# SpringReverbRev2_combined.net
KiCad netlist of a schematic drawn in EAGLE
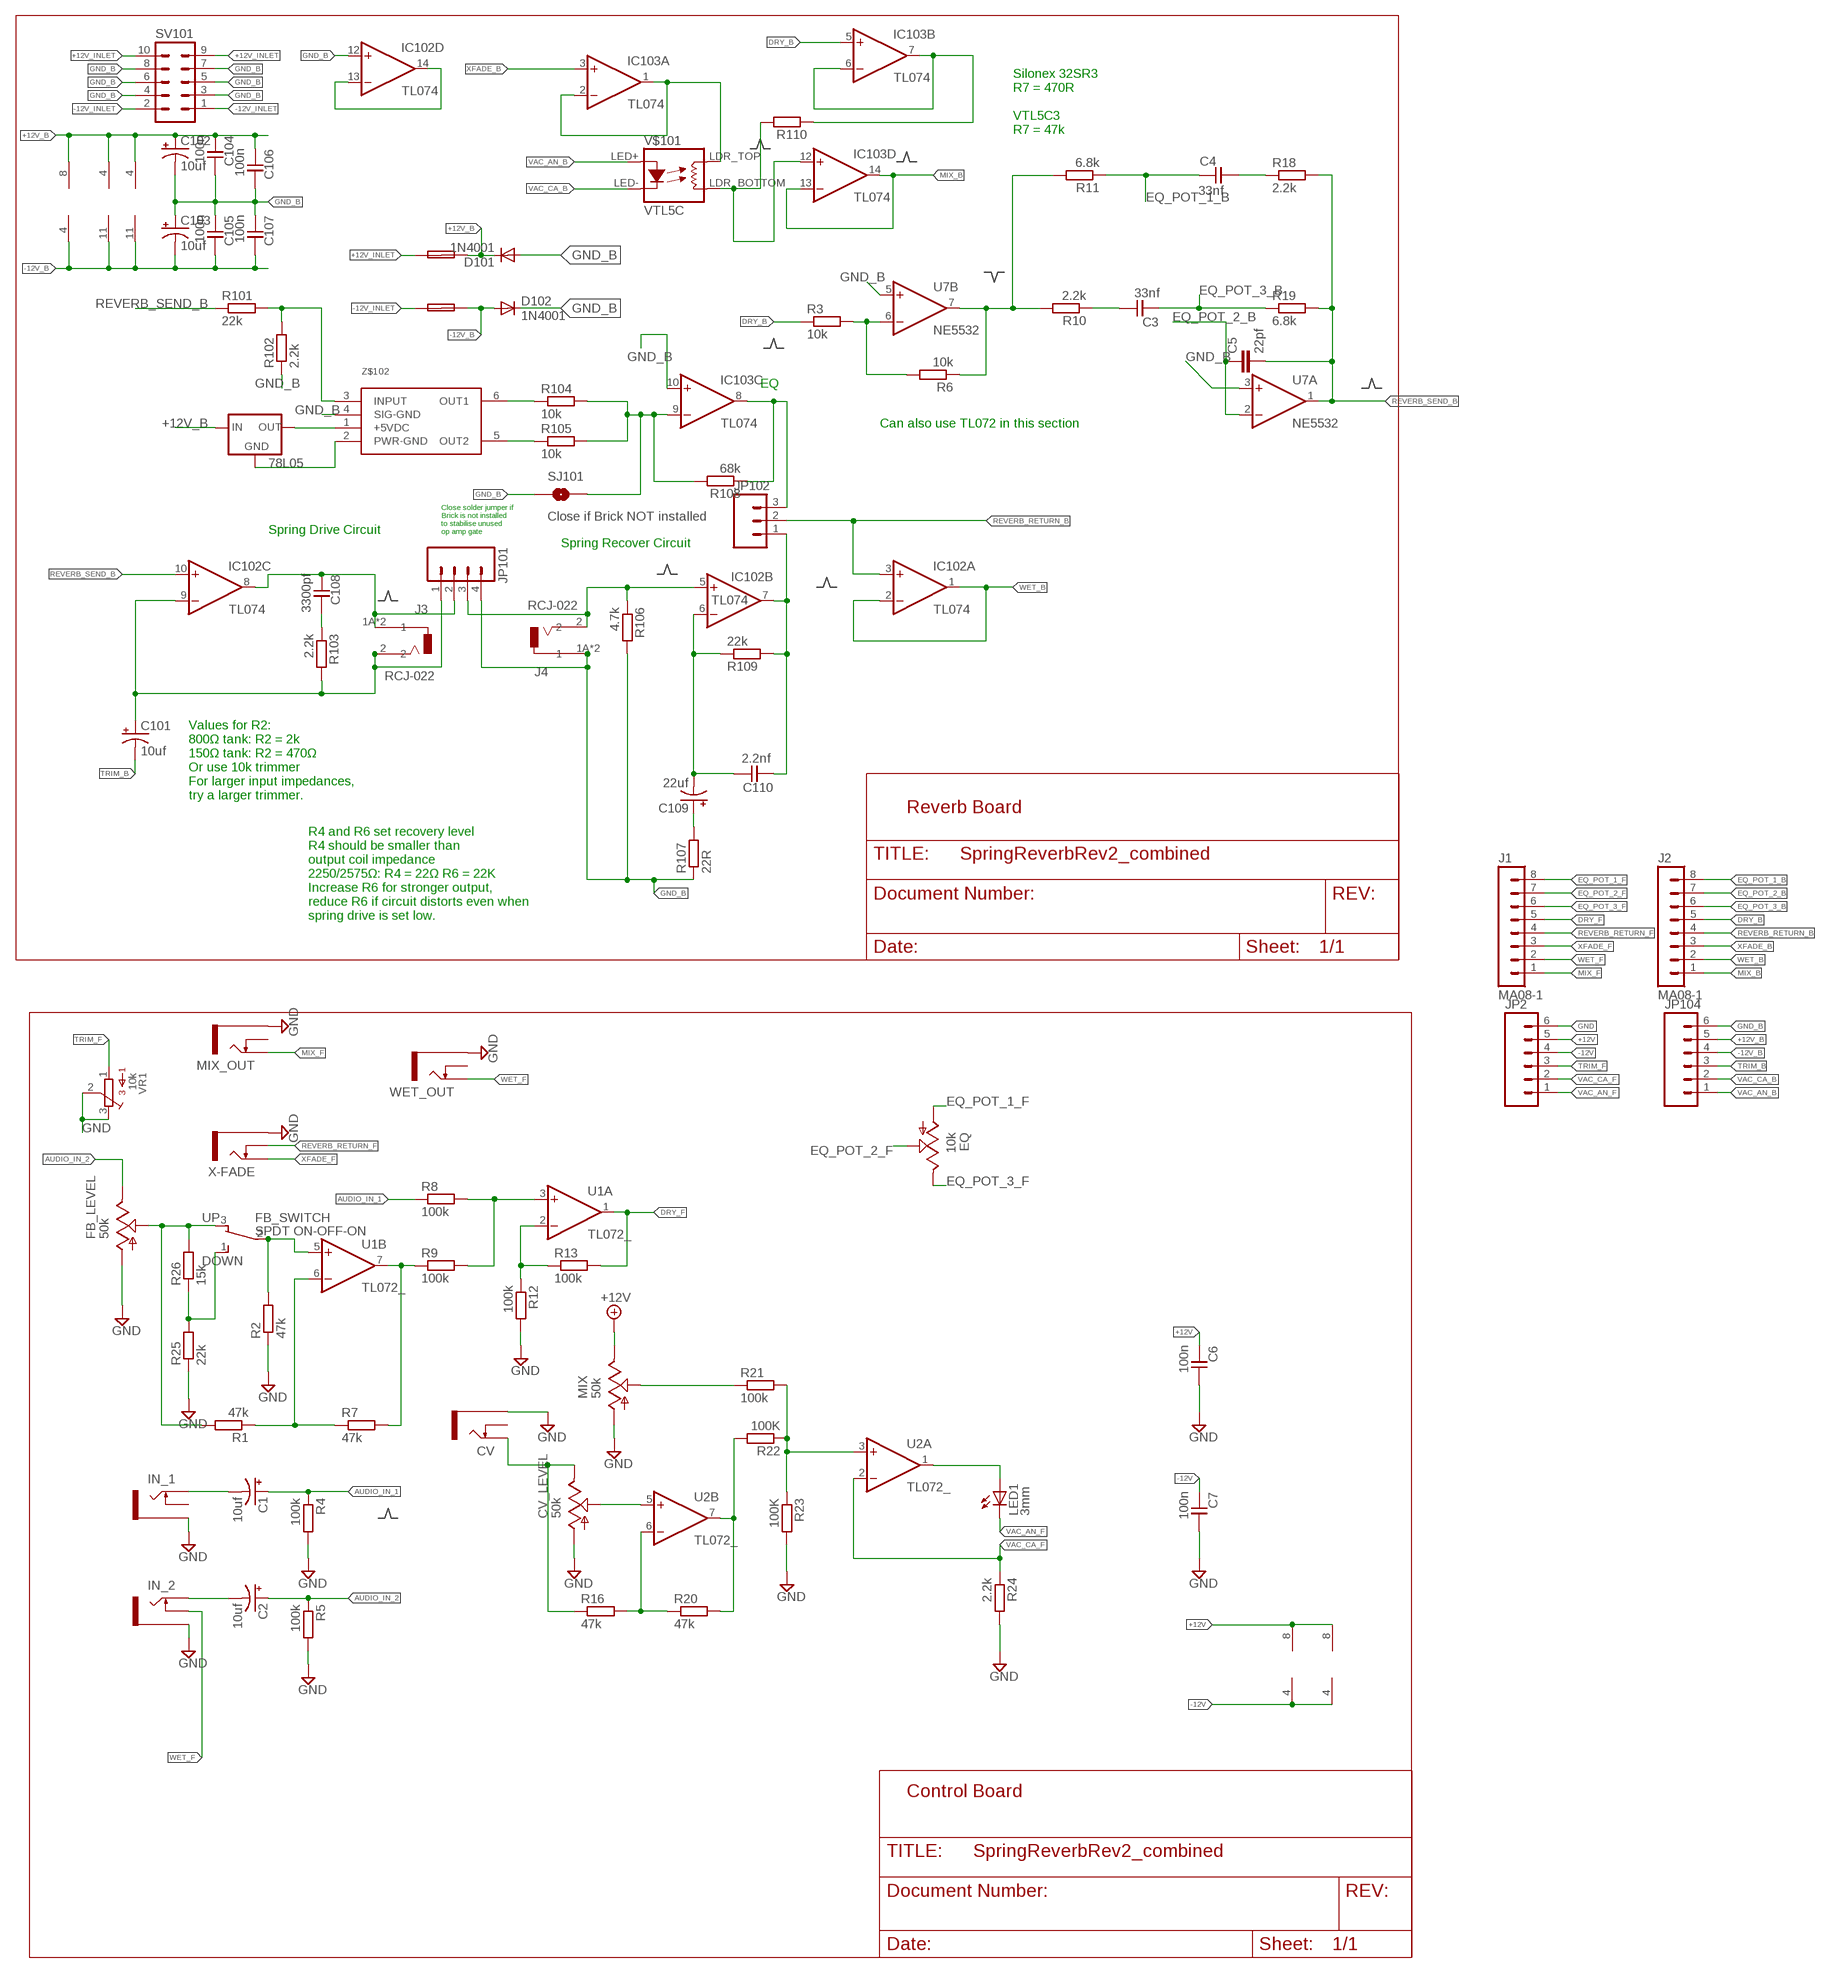
[diagram p0: schematic, sheet 1]

(export (version "E")
  (design (tool "Eeschema 10.0.6"))
  (components
    (comp (ref "78L05")
      (value "78LXX")
      (footprint "eagle-import:78LXX")
      (libsource (lib "eagle-import") (part "78LXX"))
    )
    (comp (ref "C1")
      (value "10uf")
      (footprint "eagle-import:050_020")
      (libsource (lib "eagle-import") (part "050"))
    )
    (comp (ref "C2")
      (value "10uf")
      (footprint "eagle-import:050_020")
      (libsource (lib "eagle-import") (part "050"))
    )
    (comp (ref "C3")
      (value "33nf")
      (footprint "eagle-import:C050-024X044")
      (libsource (lib "eagle-import") (part "C-EU050-024X044"))
    )
    (comp (ref "C4")
      (value "33nf")
      (footprint "eagle-import:C050-024X044")
      (libsource (lib "eagle-import") (part "C-EU050-024X044"))
    )
    (comp (ref "C5")
      (value "22pf")
      (footprint "eagle-import:050X030_025")
      (libsource (lib "eagle-import") (part "050X030_0251"))
    )
    (comp (ref "C6")
      (value "100n")
      (footprint "eagle-import:C050-024X044")
      (libsource (lib "eagle-import") (part "C-EU050-024X044"))
    )
    (comp (ref "C7")
      (value "100n")
      (footprint "eagle-import:C050-024X044")
      (libsource (lib "eagle-import") (part "C-EU050-024X044"))
    )
    (comp (ref "C101")
      (value "10uf")
      (footprint "eagle-import:CPOL-RADIAL-10UF-25V")
      (libsource (lib "eagle-import") (part "CAP_POLPTH2"))
    )
    (comp (ref "C102")
      (value "10uf")
      (footprint "eagle-import:CPOL-RADIAL-10UF-25V")
      (libsource (lib "eagle-import") (part "CAP_POLPTH2"))
    )
    (comp (ref "C103")
      (value "10uf")
      (footprint "eagle-import:CPOL-RADIAL-10UF-25V")
      (libsource (lib "eagle-import") (part "CAP_POLPTH2"))
    )
    (comp (ref "C104")
      (value "100n")
      (footprint "eagle-import:C050-024X044")
      (libsource (lib "eagle-import") (part "C-EU050-024X044"))
    )
    (comp (ref "C105")
      (value "100n")
      (footprint "eagle-import:C050-024X044")
      (libsource (lib "eagle-import") (part "C-EU050-024X044"))
    )
    (comp (ref "C106")
      (value "100n")
      (footprint "eagle-import:C050-024X044")
      (libsource (lib "eagle-import") (part "C-EU050-024X044"))
    )
    (comp (ref "C107")
      (value "100n")
      (footprint "eagle-import:C050-024X044")
      (libsource (lib "eagle-import") (part "C-EU050-024X044"))
    )
    (comp (ref "C108")
      (value "3300pf")
      (footprint "eagle-import:C050-024X044")
      (libsource (lib "eagle-import") (part "C-EU050-024X044"))
    )
    (comp (ref "C109")
      (value "22uf")
      (footprint "eagle-import:CPOL-RADIAL-10UF-25V")
      (libsource (lib "eagle-import") (part "CAP_POLPTH2"))
    )
    (comp (ref "C110")
      (value "2.2nf")
      (footprint "eagle-import:C050-024X044")
      (libsource (lib "eagle-import") (part "C-EU050-024X044"))
    )
    (comp (ref "CV")
      (value "THONKICONNNEW")
      (footprint "eagle-import:WQP-PJ301M-12_JACK")
      (libsource (lib "eagle-import") (part "THONKICONNNEW"))
    )
    (comp (ref "CV_LEVEL")
      (value "50k")
      (footprint "eagle-import:EVUF")
      (libsource (lib "eagle-import") (part "ALPHA-9MMAF2"))
    )
    (comp (ref "D101")
      (value "1N4001")
      (footprint "eagle-import:DO41-10")
      (libsource (lib "eagle-import") (part "1N4004"))
    )
    (comp (ref "D102")
      (value "1N4001")
      (footprint "eagle-import:DO41-10")
      (libsource (lib "eagle-import") (part "1N4004"))
    )
    (comp (ref "EQ")
      (value "10k")
      (footprint "eagle-import:EVUF")
      (libsource (lib "eagle-import") (part "ALPHA-9MMAF2"))
    )
    (comp (ref "F101")
      (value "FUSE")
      (footprint "eagle-import:C050H075X075")
      (libsource (lib "eagle-import") (part "PTC_FUSEPOLY_FUSE"))
    )
    (comp (ref "F102")
      (value "FUSE")
      (footprint "eagle-import:C050H075X075")
      (libsource (lib "eagle-import") (part "PTC_FUSEPOLY_FUSE"))
    )
    (comp (ref "FB_LEVEL")
      (value "50k")
      (footprint "eagle-import:EVUF")
      (libsource (lib "eagle-import") (part "ALPHA-9MMAF2"))
    )
    (comp (ref "FB_SWITCH")
      (value "SPDT ON-OFF-ON")
      (footprint "eagle-import:SPDT-VERTICAL-TOP-SUBMINI-MULTICOMP")
      (libsource (lib "eagle-import") (part "SPDT-VERTICAL-UPTOP-SUBMINI"))
    )
    (comp (ref "IC102")
      (value "TL074")
      (footprint "eagle-import:DIL14")
      (libsource (lib "eagle-import") (part "TL074P"))
    )
    (comp (ref "IC103")
      (value "TL074")
      (footprint "eagle-import:DIL14")
      (libsource (lib "eagle-import") (part "TL074P"))
    )
    (comp (ref "IN_1")
      (value "THONKICONNNEW")
      (footprint "eagle-import:WQP-PJ301M-12_JACK")
      (libsource (lib "eagle-import") (part "THONKICONNNEW"))
    )
    (comp (ref "IN_2")
      (value "THONKICONNNEW")
      (footprint "eagle-import:WQP-PJ301M-12_JACK")
      (libsource (lib "eagle-import") (part "THONKICONNNEW"))
    )
    (comp (ref "J1")
      (value "MA08-1")
      (footprint "eagle-import:MA08-1")
      (libsource (lib "eagle-import") (part "MA08-1"))
    )
    (comp (ref "J2")
      (value "MA08-1")
      (footprint "eagle-import:MA08-1")
      (libsource (lib "eagle-import") (part "MA08-1"))
    )
    (comp (ref "J3")
      (value "RCJ-022")
      (footprint "eagle-import:CUI_RCJ-022")
      (fields (field (name "MANUFACTURER") "CUI Inc"))
      (libsource (lib "eagle-import") (part "RCJ-022"))
    )
    (comp (ref "J4")
      (value "RCJ-022")
      (footprint "eagle-import:CUI_RCJ-022")
      (fields (field (name "MANUFACTURER") "CUI Inc"))
      (libsource (lib "eagle-import") (part "RCJ-022"))
    )
    (comp (ref "JP2")
      (value "M06SIP")
      (footprint "eagle-import:1X06")
      (libsource (lib "eagle-import") (part "M06SIP"))
    )
    (comp (ref "JP101")
      (value "M04POLAR")
      (footprint "eagle-import:MOLEX-1X4")
      (libsource (lib "eagle-import") (part "M04POLAR"))
    )
    (comp (ref "JP102")
      (value "M03LOCK_NO_SILK")
      (footprint "eagle-import:1X03_LOCK_NO_SILK")
      (libsource (lib "eagle-import") (part "M03LOCK_NO_SILK"))
    )
    (comp (ref "JP104")
      (value "M06SIP")
      (footprint "eagle-import:1X06")
      (libsource (lib "eagle-import") (part "M06SIP"))
    )
    (comp (ref "LED1")
      (value "3mm")
      (footprint "eagle-import:LED3MM")
      (libsource (lib "eagle-import") (part "LED3MM"))
    )
    (comp (ref "MIX")
      (value "50k")
      (footprint "eagle-import:EVUF")
      (libsource (lib "eagle-import") (part "ALPHA-9MMAF2"))
    )
    (comp (ref "MIX_OUT")
      (value "THONKICONNNEW")
      (footprint "eagle-import:WQP-PJ301M-12_JACK")
      (libsource (lib "eagle-import") (part "THONKICONNNEW"))
    )
    (comp (ref "R1")
      (value "47k")
      (footprint "eagle-import:7MM_RESISTOR")
      (libsource (lib "eagle-import") (part "RESISTOR7MM"))
    )
    (comp (ref "R2")
      (value "47k")
      (footprint "eagle-import:7MM_RESISTOR")
      (libsource (lib "eagle-import") (part "RESISTOR7MM"))
    )
    (comp (ref "R3")
      (value "10k")
      (footprint "eagle-import:7MM_RESISTOR")
      (libsource (lib "eagle-import") (part "RESISTOR7MM"))
    )
    (comp (ref "R4")
      (value "100k")
      (footprint "eagle-import:7MM_RESISTOR")
      (libsource (lib "eagle-import") (part "RESISTOR7MM"))
    )
    (comp (ref "R5")
      (value "100k")
      (footprint "eagle-import:7MM_RESISTOR")
      (libsource (lib "eagle-import") (part "RESISTOR7MM"))
    )
    (comp (ref "R6")
      (value "10k")
      (footprint "eagle-import:7MM_RESISTOR")
      (libsource (lib "eagle-import") (part "RESISTOR7MM"))
    )
    (comp (ref "R7")
      (value "47k")
      (footprint "eagle-import:7MM_RESISTOR")
      (libsource (lib "eagle-import") (part "RESISTOR7MM"))
    )
    (comp (ref "R8")
      (value "100k")
      (footprint "eagle-import:7MM_RESISTOR")
      (libsource (lib "eagle-import") (part "RESISTOR7MM"))
    )
    (comp (ref "R9")
      (value "100k")
      (footprint "eagle-import:7MM_RESISTOR")
      (libsource (lib "eagle-import") (part "RESISTOR7MM"))
    )
    (comp (ref "R10")
      (value "2.2k")
      (footprint "eagle-import:7MM_RESISTOR")
      (libsource (lib "eagle-import") (part "RESISTOR7MM"))
    )
    (comp (ref "R11")
      (value "6.8k")
      (footprint "eagle-import:7MM_RESISTOR")
      (libsource (lib "eagle-import") (part "RESISTOR7MM"))
    )
    (comp (ref "R12")
      (value "100k")
      (footprint "eagle-import:7MM_RESISTOR")
      (libsource (lib "eagle-import") (part "RESISTOR7MM"))
    )
    (comp (ref "R13")
      (value "100k")
      (footprint "eagle-import:7MM_RESISTOR")
      (libsource (lib "eagle-import") (part "RESISTOR7MM"))
    )
    (comp (ref "R16")
      (value "47k")
      (footprint "eagle-import:7MM_RESISTOR")
      (libsource (lib "eagle-import") (part "RESISTOR7MM"))
    )
    (comp (ref "R18")
      (value "2.2k")
      (footprint "eagle-import:7MM_RESISTOR")
      (libsource (lib "eagle-import") (part "RESISTOR7MM"))
    )
    (comp (ref "R19")
      (value "6.8k")
      (footprint "eagle-import:7MM_RESISTOR")
      (libsource (lib "eagle-import") (part "RESISTOR7MM"))
    )
    (comp (ref "R20")
      (value "47k")
      (footprint "eagle-import:7MM_RESISTOR")
      (libsource (lib "eagle-import") (part "RESISTOR7MM"))
    )
    (comp (ref "R21")
      (value "100k")
      (footprint "eagle-import:7MM_RESISTOR")
      (libsource (lib "eagle-import") (part "RESISTOR7MM"))
    )
    (comp (ref "R22")
      (value "100K")
      (footprint "eagle-import:7MM_RESISTOR")
      (libsource (lib "eagle-import") (part "RESISTOR7MM"))
    )
    (comp (ref "R23")
      (value "100K")
      (footprint "eagle-import:7MM_RESISTOR")
      (libsource (lib "eagle-import") (part "RESISTOR7MM"))
    )
    (comp (ref "R24")
      (value "2.2k")
      (footprint "eagle-import:7MM_RESISTOR")
      (libsource (lib "eagle-import") (part "RESISTOR7MM"))
    )
    (comp (ref "R25")
      (value "22k")
      (footprint "eagle-import:7MM_RESISTOR")
      (libsource (lib "eagle-import") (part "RESISTOR7MM"))
    )
    (comp (ref "R26")
      (value "15k")
      (footprint "eagle-import:7MM_RESISTOR")
      (libsource (lib "eagle-import") (part "RESISTOR7MM"))
    )
    (comp (ref "R101")
      (value "22k")
      (footprint "eagle-import:7MM_RESISTOR")
      (libsource (lib "eagle-import") (part "RESISTOR7MM"))
    )
    (comp (ref "R102")
      (value "2.2k")
      (footprint "eagle-import:7MM_RESISTOR")
      (libsource (lib "eagle-import") (part "RESISTOR7MM"))
    )
    (comp (ref "R103")
      (value "2.2k")
      (footprint "eagle-import:7MM_RESISTOR")
      (libsource (lib "eagle-import") (part "RESISTOR7MM"))
    )
    (comp (ref "R104")
      (value "10k")
      (footprint "eagle-import:7MM_RESISTOR")
      (libsource (lib "eagle-import") (part "RESISTOR7MM"))
    )
    (comp (ref "R105")
      (value "10k")
      (footprint "eagle-import:7MM_RESISTOR")
      (libsource (lib "eagle-import") (part "RESISTOR7MM"))
    )
    (comp (ref "R106")
      (value "4.7k")
      (footprint "eagle-import:7MM_RESISTOR")
      (libsource (lib "eagle-import") (part "RESISTOR7MM"))
    )
    (comp (ref "R107")
      (value "22R")
      (footprint "eagle-import:7MM_RESISTOR")
      (libsource (lib "eagle-import") (part "RESISTOR7MM"))
    )
    (comp (ref "R108")
      (value "68k")
      (footprint "eagle-import:7MM_RESISTOR")
      (libsource (lib "eagle-import") (part "RESISTOR7MM"))
    )
    (comp (ref "R109")
      (value "22k")
      (footprint "eagle-import:7MM_RESISTOR")
      (libsource (lib "eagle-import") (part "RESISTOR7MM"))
    )
    (comp (ref "R110")
      (value "RESISTOR7MM")
      (footprint "eagle-import:7MM_RESISTOR")
      (libsource (lib "eagle-import") (part "RESISTOR7MM"))
    )
    (comp (ref "SJ101")
      (value "Close if Brick NOT installed")
      (footprint "eagle-import:SJ_2S-NOTRACE")
      (libsource (lib "eagle-import") (part "SOLDERJUMPERNC2"))
    )
    (comp (ref "SV101")
      (value "10_PIN_HEADER")
      (footprint "eagle-import:MA05-2")
      (libsource (lib "eagle-import") (part "10_PIN_HEADER"))
    )
    (comp (ref "U1")
      (value "TL072_")
      (footprint "eagle-import:DIL08")
      (libsource (lib "eagle-import") (part "TL072_"))
    )
    (comp (ref "U2")
      (value "TL072_")
      (footprint "eagle-import:DIL08")
      (libsource (lib "eagle-import") (part "TL072_"))
    )
    (comp (ref "U7")
      (value "NE5532")
      (footprint "eagle-import:DIL08")
      (libsource (lib "eagle-import") (part "TL072_"))
    )
    (comp (ref "V$101")
      (value "VTL5C")
      (footprint "eagle-import:VACTROL_COMPACT")
      (libsource (lib "eagle-import") (part "VACTROL_COMPACT"))
    )
    (comp (ref "VR1")
      (value "10k")
      (footprint "eagle-import:BOURNS_3362P_TRIMMER")
      (libsource (lib "eagle-import") (part "BOURNS_3362P_TRIMMERP"))
    )
    (comp (ref "WET_OUT")
      (value "THONKICONNNEW")
      (footprint "eagle-import:WQP-PJ301M-12_JACK")
      (libsource (lib "eagle-import") (part "THONKICONNNEW"))
    )
    (comp (ref "X-FADE")
      (value "THONKICONNNEW")
      (footprint "eagle-import:WQP-PJ301M-12_JACK")
      (libsource (lib "eagle-import") (part "THONKICONNNEW"))
    )
    (comp (ref "Z$102")
      (value "BTDR-2H")
      (footprint "eagle-import:BTDR-2H")
      (libsource (lib "eagle-import") (part "BTDR-2H"))
    )
  )
  (nets
    (net (code "1") (name "+12V") (class "Default")
      (node (ref "C6") (pin "2") (pinfunction "2_2") (pintype "passive"))
      (node (ref "JP2") (pin "5") (pinfunction "5_5") (pintype "passive"))
      (node (ref "MIX") (pin "3") (pinfunction "E_3") (pintype "passive"))
      (node (ref "U1") (pin "8") (pinfunction "V+_8") (pintype "power_in"))
      (node (ref "U2") (pin "8") (pinfunction "V+_8") (pintype "power_in"))
    )
    (net (code "2") (name "+12V_B") (class "Default")
      (node (ref "78L05") (pin "IN") (pinfunction "IN_IN") (pintype "input"))
      (node (ref "C102") (pin "1") (pinfunction "+_1") (pintype "passive"))
      (node (ref "C104") (pin "2") (pinfunction "2_2") (pintype "passive"))
      (node (ref "C106") (pin "2") (pinfunction "2_2") (pintype "passive"))
      (node (ref "D101") (pin "C") (pinfunction "C_C") (pintype "passive"))
      (node (ref "F101") (pin "1") (pinfunction "P$1_1") (pintype "bidirectional"))
      (node (ref "IC102") (pin "4") (pinfunction "V+_4") (pintype "power_in"))
      (node (ref "IC103") (pin "4") (pinfunction "V+_4") (pintype "power_in"))
      (node (ref "JP104") (pin "5") (pinfunction "5_5") (pintype "passive"))
      (node (ref "U7") (pin "8") (pinfunction "V+_8") (pintype "power_in"))
    )
    (net (code "3") (name "+12V_INLET") (class "Default")
      (node (ref "F101") (pin "2") (pinfunction "P$2_2") (pintype "bidirectional"))
      (node (ref "SV101") (pin "10") (pinfunction "10_10") (pintype "passive"))
      (node (ref "SV101") (pin "9") (pinfunction "9_9") (pintype "passive"))
    )
    (net (code "4") (name "-12V") (class "Default")
      (node (ref "C7") (pin "2") (pinfunction "2_2") (pintype "passive"))
      (node (ref "JP2") (pin "4") (pinfunction "4_4") (pintype "passive"))
      (node (ref "U1") (pin "4") (pinfunction "V-_4") (pintype "power_in"))
      (node (ref "U2") (pin "4") (pinfunction "V-_4") (pintype "power_in"))
    )
    (net (code "5") (name "-12V_B") (class "Default")
      (node (ref "C103") (pin "2") (pinfunction "-_2") (pintype "passive"))
      (node (ref "C105") (pin "1") (pinfunction "1_1") (pintype "passive"))
      (node (ref "C107") (pin "1") (pinfunction "1_1") (pintype "passive"))
      (node (ref "D102") (pin "A") (pinfunction "A_A") (pintype "passive"))
      (node (ref "F102") (pin "1") (pinfunction "P$1_1") (pintype "bidirectional"))
      (node (ref "IC102") (pin "11") (pinfunction "V-_11") (pintype "power_in"))
      (node (ref "IC103") (pin "11") (pinfunction "V-_11") (pintype "power_in"))
      (node (ref "JP104") (pin "4") (pinfunction "4_4") (pintype "passive"))
      (node (ref "U7") (pin "4") (pinfunction "V-_4") (pintype "power_in"))
    )
    (net (code "6") (name "-12V_INLET") (class "Default")
      (node (ref "F102") (pin "2") (pinfunction "P$2_2") (pintype "bidirectional"))
      (node (ref "SV101") (pin "1") (pinfunction "1_1") (pintype "passive"))
      (node (ref "SV101") (pin "2") (pinfunction "2_2") (pintype "passive"))
    )
    (net (code "7") (name "AUDIO_IN_1") (class "Default")
      (node (ref "C1") (pin "+") (pinfunction "+_+") (pintype "passive"))
      (node (ref "R4") (pin "1") (pinfunction "1_1") (pintype "passive"))
      (node (ref "R8") (pin "1") (pinfunction "1_1") (pintype "passive"))
    )
    (net (code "8") (name "AUDIO_IN_2") (class "Default")
      (node (ref "C2") (pin "+") (pinfunction "+_+") (pintype "passive"))
      (node (ref "FB_LEVEL") (pin "3") (pinfunction "E_3") (pintype "passive"))
      (node (ref "R5") (pin "1") (pinfunction "1_1") (pintype "passive"))
    )
    (net (code "9") (name "DRY_B") (class "Default")
      (node (ref "IC103") (pin "5") (pinfunction "+IN_5") (pintype "input"))
      (node (ref "J2") (pin "5") (pinfunction "5_5") (pintype "passive"))
      (node (ref "R3") (pin "1") (pinfunction "1_1") (pintype "passive"))
    )
    (net (code "10") (name "DRY_F") (class "Default")
      (node (ref "J1") (pin "5") (pinfunction "5_5") (pintype "passive"))
      (node (ref "R13") (pin "2") (pinfunction "2_2") (pintype "passive"))
      (node (ref "U1") (pin "1") (pinfunction "OUT_1") (pintype "output"))
    )
    (net (code "11") (name "EQ_POT_1_B") (class "Default")
      (node (ref "C4") (pin "2") (pinfunction "2_2") (pintype "passive"))
      (node (ref "J2") (pin "8") (pinfunction "8_8") (pintype "passive"))
      (node (ref "R11") (pin "1") (pinfunction "1_1") (pintype "passive"))
    )
    (net (code "12") (name "EQ_POT_1_F") (class "Default")
      (node (ref "EQ") (pin "1") (pinfunction "A_1") (pintype "passive"))
      (node (ref "J1") (pin "8") (pinfunction "8_8") (pintype "passive"))
    )
    (net (code "13") (name "EQ_POT_2_B") (class "Default")
      (node (ref "C5") (pin "1") (pinfunction "1_1") (pintype "passive"))
      (node (ref "J2") (pin "7") (pinfunction "7_7") (pintype "passive"))
      (node (ref "U7") (pin "2") (pinfunction "-IN_2") (pintype "input"))
    )
    (net (code "14") (name "EQ_POT_2_F") (class "Default")
      (node (ref "EQ") (pin "2") (pinfunction "S_2") (pintype "passive"))
      (node (ref "J1") (pin "7") (pinfunction "7_7") (pintype "passive"))
    )
    (net (code "15") (name "EQ_POT_3_B") (class "Default")
      (node (ref "C3") (pin "2") (pinfunction "2_2") (pintype "passive"))
      (node (ref "J2") (pin "6") (pinfunction "6_6") (pintype "passive"))
      (node (ref "R19") (pin "1") (pinfunction "1_1") (pintype "passive"))
    )
    (net (code "16") (name "EQ_POT_3_F") (class "Default")
      (node (ref "EQ") (pin "3") (pinfunction "E_3") (pintype "passive"))
      (node (ref "J1") (pin "6") (pinfunction "6_6") (pintype "passive"))
    )
    (net (code "17") (name "GND") (class "Default")
      (node (ref "C6") (pin "1") (pinfunction "1_1") (pintype "passive"))
      (node (ref "C7") (pin "1") (pinfunction "1_1") (pintype "passive"))
      (node (ref "CV") (pin "P$3_SLEEVE") (pinfunction "SLEEVE_P$3_SLEEVE") (pintype "passive"))
      (node (ref "CV_LEVEL") (pin "1") (pinfunction "A_1") (pintype "passive"))
      (node (ref "FB_LEVEL") (pin "1") (pinfunction "A_1") (pintype "passive"))
      (node (ref "IN_1") (pin "P$3_SLEEVE") (pinfunction "SLEEVE_P$3_SLEEVE") (pintype "passive"))
      (node (ref "IN_2") (pin "P$3_SLEEVE") (pinfunction "SLEEVE_P$3_SLEEVE") (pintype "passive"))
      (node (ref "JP2") (pin "6") (pinfunction "6_6") (pintype "passive"))
      (node (ref "MIX") (pin "1") (pinfunction "A_1") (pintype "passive"))
      (node (ref "MIX_OUT") (pin "P$3_SLEEVE") (pinfunction "SLEEVE_P$3_SLEEVE") (pintype "passive"))
      (node (ref "R12") (pin "2") (pinfunction "2_2") (pintype "passive"))
      (node (ref "R2") (pin "1") (pinfunction "1_1") (pintype "passive"))
      (node (ref "R23") (pin "2") (pinfunction "2_2") (pintype "passive"))
      (node (ref "R24") (pin "2") (pinfunction "2_2") (pintype "passive"))
      (node (ref "R25") (pin "1") (pinfunction "1_1") (pintype "passive"))
      (node (ref "R4") (pin "2") (pinfunction "2_2") (pintype "passive"))
      (node (ref "R5") (pin "2") (pinfunction "2_2") (pintype "passive"))
      (node (ref "VR1") (pin "2") (pinfunction "2_2") (pintype "passive"))
      (node (ref "VR1") (pin "3") (pinfunction "3_3") (pintype "passive"))
      (node (ref "WET_OUT") (pin "P$3_SLEEVE") (pinfunction "SLEEVE_P$3_SLEEVE") (pintype "passive"))
      (node (ref "X-FADE") (pin "P$3_SLEEVE") (pinfunction "SLEEVE_P$3_SLEEVE") (pintype "passive"))
    )
    (net (code "18") (name "GND_B") (class "Default")
      (node (ref "C102") (pin "2") (pinfunction "-_2") (pintype "passive"))
      (node (ref "C103") (pin "1") (pinfunction "+_1") (pintype "passive"))
      (node (ref "C104") (pin "1") (pinfunction "1_1") (pintype "passive"))
      (node (ref "C105") (pin "2") (pinfunction "2_2") (pintype "passive"))
      (node (ref "C106") (pin "1") (pinfunction "1_1") (pintype "passive"))
      (node (ref "C107") (pin "2") (pinfunction "2_2") (pintype "passive"))
      (node (ref "D101") (pin "A") (pinfunction "A_A") (pintype "passive"))
      (node (ref "D102") (pin "C") (pinfunction "C_C") (pintype "passive"))
      (node (ref "IC102") (pin "12") (pinfunction "+IN_12") (pintype "input"))
      (node (ref "IC103") (pin "10") (pinfunction "+IN_10") (pintype "input"))
      (node (ref "J4") (pin "1A") (pinfunction "1_1A") (pintype "passive"))
      (node (ref "J4") (pin "1B") (pinfunction "1_1B") (pintype "passive"))
      (node (ref "JP101") (pin "4") (pinfunction "4_4") (pintype "passive"))
      (node (ref "JP104") (pin "6") (pinfunction "6_6") (pintype "passive"))
      (node (ref "R102") (pin "1") (pinfunction "1_1") (pintype "passive"))
      (node (ref "R106") (pin "2") (pinfunction "2_2") (pintype "passive"))
      (node (ref "R107") (pin "1") (pinfunction "1_1") (pintype "passive"))
      (node (ref "SJ101") (pin "1") (pinfunction "1_1") (pintype "passive"))
      (node (ref "SV101") (pin "3") (pinfunction "3_3") (pintype "passive"))
      (node (ref "SV101") (pin "4") (pinfunction "4_4") (pintype "passive"))
      (node (ref "SV101") (pin "5") (pinfunction "5_5") (pintype "passive"))
      (node (ref "SV101") (pin "6") (pinfunction "6_6") (pintype "passive"))
      (node (ref "SV101") (pin "7") (pinfunction "7_7") (pintype "passive"))
      (node (ref "SV101") (pin "8") (pinfunction "8_8") (pintype "passive"))
      (node (ref "U7") (pin "3") (pinfunction "+IN_3") (pintype "input"))
      (node (ref "U7") (pin "5") (pinfunction "+IN_5") (pintype "input"))
      (node (ref "Z$102") (pin "4") (pinfunction "SIG-GND_4") (pintype "bidirectional"))
    )
    (net (code "19") (name "MIX_B") (class "Default")
      (node (ref "IC103") (pin "13") (pinfunction "-IN_13") (pintype "input"))
      (node (ref "IC103") (pin "14") (pinfunction "OUT_14") (pintype "output"))
      (node (ref "J2") (pin "1") (pinfunction "1_1") (pintype "passive"))
    )
    (net (code "20") (name "MIX_F") (class "Default")
      (node (ref "J1") (pin "1") (pinfunction "1_1") (pintype "passive"))
      (node (ref "MIX_OUT") (pin "P$1_TIP") (pinfunction "TIP_P$1_TIP") (pintype "passive"))
    )
    (net (code "21") (name "Net-(C3-Pad1)") (class "Default")
      (node (ref "C3") (pin "1") (pinfunction "1_1") (pintype "passive"))
      (node (ref "R10") (pin "1") (pinfunction "1_1") (pintype "passive"))
    )
    (net (code "22") (name "Net-(C4-Pad1)") (class "Default")
      (node (ref "C4") (pin "1") (pinfunction "1_1") (pintype "passive"))
      (node (ref "R18") (pin "1") (pinfunction "1_1") (pintype "passive"))
    )
    (net (code "23") (name "Net-(C101-+)") (class "Default")
      (node (ref "C101") (pin "1") (pinfunction "+_1") (pintype "passive"))
      (node (ref "IC102") (pin "9") (pinfunction "-IN_9") (pintype "input"))
      (node (ref "J3") (pin "2") (pinfunction "2_2") (pintype "passive"))
      (node (ref "JP101") (pin "1") (pinfunction "1_1") (pintype "passive"))
      (node (ref "R103") (pin "2") (pinfunction "2_2") (pintype "passive"))
    )
    (net (code "24") (name "Net-(C108-Pad1)") (class "Default")
      (node (ref "C108") (pin "1") (pinfunction "1_1") (pintype "passive"))
      (node (ref "R103") (pin "1") (pinfunction "1_1") (pintype "passive"))
    )
    (net (code "25") (name "Net-(C109-+)") (class "Default")
      (node (ref "C109") (pin "1") (pinfunction "+_1") (pintype "passive"))
      (node (ref "R107") (pin "2") (pinfunction "2_2") (pintype "passive"))
    )
    (net (code "26") (name "Net-(C109--)") (class "Default")
      (node (ref "C109") (pin "2") (pinfunction "-_2") (pintype "passive"))
      (node (ref "C110") (pin "1") (pinfunction "1_1") (pintype "passive"))
      (node (ref "IC102") (pin "6") (pinfunction "-IN_6") (pintype "input"))
      (node (ref "R109") (pin "1") (pinfunction "1_1") (pintype "passive"))
    )
    (net (code "27") (name "Net-(CV-TIP)") (class "Default")
      (node (ref "CV") (pin "P$1_TIP") (pinfunction "TIP_P$1_TIP") (pintype "passive"))
      (node (ref "CV_LEVEL") (pin "3") (pinfunction "E_3") (pintype "passive"))
      (node (ref "R16") (pin "1") (pinfunction "1_1") (pintype "passive"))
    )
    (net (code "28") (name "Net-(CV_LEVEL-S)") (class "Default")
      (node (ref "CV_LEVEL") (pin "2") (pinfunction "S_2") (pintype "passive"))
      (node (ref "U2") (pin "5") (pinfunction "+IN_5") (pintype "input"))
    )
    (net (code "29") (name "Net-(FB_LEVEL-S)") (class "Default")
      (node (ref "FB_LEVEL") (pin "2") (pinfunction "S_2") (pintype "passive"))
      (node (ref "FB_SWITCH") (pin "3") (pinfunction "3_3") (pintype "passive"))
      (node (ref "R1") (pin "2") (pinfunction "2_2") (pintype "passive"))
      (node (ref "R26") (pin "2") (pinfunction "2_2") (pintype "passive"))
    )
    (net (code "30") (name "Net-(FB_SWITCH-Pad1)") (class "Default")
      (node (ref "FB_SWITCH") (pin "1") (pinfunction "1_1") (pintype "passive"))
      (node (ref "R25") (pin "2") (pinfunction "2_2") (pintype "passive"))
      (node (ref "R26") (pin "1") (pinfunction "1_1") (pintype "passive"))
    )
    (net (code "31") (name "Net-(IC102B-+IN)") (class "Default")
      (node (ref "IC102") (pin "5") (pinfunction "+IN_5") (pintype "input"))
      (node (ref "J4") (pin "2") (pinfunction "2_2") (pintype "passive"))
      (node (ref "JP101") (pin "3") (pinfunction "3_3") (pintype "passive"))
      (node (ref "R106") (pin "1") (pinfunction "1_1") (pintype "passive"))
    )
    (net (code "32") (name "Net-(IC102B-OUT)") (class "Default")
      (node (ref "C110") (pin "2") (pinfunction "2_2") (pintype "passive"))
      (node (ref "IC102") (pin "7") (pinfunction "OUT_7") (pintype "output"))
      (node (ref "JP102") (pin "1") (pinfunction "1_1") (pintype "passive"))
      (node (ref "R109") (pin "2") (pinfunction "2_2") (pintype "passive"))
    )
    (net (code "33") (name "Net-(IC102C-OUT)") (class "Default")
      (node (ref "C108") (pin "2") (pinfunction "2_2") (pintype "passive"))
      (node (ref "IC102") (pin "8") (pinfunction "OUT_8") (pintype "output"))
      (node (ref "J3") (pin "1A") (pinfunction "1_1A") (pintype "passive"))
      (node (ref "J3") (pin "1B") (pinfunction "1_1B") (pintype "passive"))
      (node (ref "JP101") (pin "2") (pinfunction "2_2") (pintype "passive"))
    )
    (net (code "34") (name "Net-(IC102D--IN)") (class "Default")
      (node (ref "IC102") (pin "13") (pinfunction "-IN_13") (pintype "input"))
      (node (ref "IC102") (pin "14") (pinfunction "OUT_14") (pintype "output"))
    )
    (net (code "35") (name "Net-(IC103A--IN)") (class "Default")
      (node (ref "IC103") (pin "1") (pinfunction "OUT_1") (pintype "output"))
      (node (ref "IC103") (pin "2") (pinfunction "-IN_2") (pintype "input"))
      (node (ref "V$101") (pin "LDR_TOP") (pinfunction "RES1_LDR_TOP") (pintype "passive"))
    )
    (net (code "36") (name "Net-(IC103B--IN)") (class "Default")
      (node (ref "IC103") (pin "6") (pinfunction "-IN_6") (pintype "input"))
      (node (ref "IC103") (pin "7") (pinfunction "OUT_7") (pintype "output"))
      (node (ref "R110") (pin "1") (pinfunction "1_1") (pintype "passive"))
    )
    (net (code "37") (name "Net-(IC103C--IN)") (class "Default")
      (node (ref "IC103") (pin "9") (pinfunction "-IN_9") (pintype "input"))
      (node (ref "R104") (pin "2") (pinfunction "2_2") (pintype "passive"))
      (node (ref "R105") (pin "2") (pinfunction "2_2") (pintype "passive"))
      (node (ref "R108") (pin "2") (pinfunction "2_2") (pintype "passive"))
      (node (ref "SJ101") (pin "2") (pinfunction "2_2") (pintype "passive"))
    )
    (net (code "38") (name "Net-(IC103C-OUT)") (class "Default")
      (node (ref "IC103") (pin "8") (pinfunction "OUT_8") (pintype "output"))
      (node (ref "JP102") (pin "3") (pinfunction "3_3") (pintype "passive"))
      (node (ref "R108") (pin "1") (pinfunction "1_1") (pintype "passive"))
    )
    (net (code "39") (name "Net-(IC103D-+IN)") (class "Default")
      (node (ref "IC103") (pin "12") (pinfunction "+IN_12") (pintype "input"))
      (node (ref "R110") (pin "2") (pinfunction "2_2") (pintype "passive"))
      (node (ref "V$101") (pin "LDR_BOTTOM") (pinfunction "RES2_LDR_BOTTOM") (pintype "passive"))
    )
    (net (code "40") (name "Net-(IN_1-TIP)") (class "Default")
      (node (ref "C1") (pin "-") (pinfunction "-_-") (pintype "passive"))
      (node (ref "IN_1") (pin "P$1_TIP") (pinfunction "TIP_P$1_TIP") (pintype "passive"))
    )
    (net (code "41") (name "Net-(IN_2-TIP)") (class "Default")
      (node (ref "C2") (pin "-") (pinfunction "-_-") (pintype "passive"))
      (node (ref "IN_2") (pin "P$1_TIP") (pinfunction "TIP_P$1_TIP") (pintype "passive"))
    )
    (net (code "42") (name "Net-(MIX-S)") (class "Default")
      (node (ref "MIX") (pin "2") (pinfunction "S_2") (pintype "passive"))
      (node (ref "R21") (pin "1") (pinfunction "1_1") (pintype "passive"))
    )
    (net (code "43") (name "Net-(U1A-+IN)") (class "Default")
      (node (ref "R8") (pin "2") (pinfunction "2_2") (pintype "passive"))
      (node (ref "R9") (pin "2") (pinfunction "2_2") (pintype "passive"))
      (node (ref "U1") (pin "3") (pinfunction "+IN_3") (pintype "input"))
    )
    (net (code "44") (name "Net-(U1A--IN)") (class "Default")
      (node (ref "R12") (pin "1") (pinfunction "1_1") (pintype "passive"))
      (node (ref "R13") (pin "1") (pinfunction "1_1") (pintype "passive"))
      (node (ref "U1") (pin "2") (pinfunction "-IN_2") (pintype "input"))
    )
    (net (code "45") (name "Net-(U1B-+IN)") (class "Default")
      (node (ref "FB_SWITCH") (pin "2") (pinfunction "2_2") (pintype "passive"))
      (node (ref "R2") (pin "2") (pinfunction "2_2") (pintype "passive"))
      (node (ref "U1") (pin "5") (pinfunction "+IN_5") (pintype "input"))
    )
    (net (code "46") (name "Net-(U1B--IN)") (class "Default")
      (node (ref "R1") (pin "1") (pinfunction "1_1") (pintype "passive"))
      (node (ref "R7") (pin "1") (pinfunction "1_1") (pintype "passive"))
      (node (ref "U1") (pin "6") (pinfunction "-IN_6") (pintype "input"))
    )
    (net (code "47") (name "Net-(U1B-OUT)") (class "Default")
      (node (ref "R7") (pin "2") (pinfunction "2_2") (pintype "passive"))
      (node (ref "R9") (pin "1") (pinfunction "1_1") (pintype "passive"))
      (node (ref "U1") (pin "7") (pinfunction "OUT_7") (pintype "output"))
    )
    (net (code "48") (name "Net-(U2A-+IN)") (class "Default")
      (node (ref "R21") (pin "2") (pinfunction "2_2") (pintype "passive"))
      (node (ref "R22") (pin "1") (pinfunction "1_1") (pintype "passive"))
      (node (ref "R23") (pin "1") (pinfunction "1_1") (pintype "passive"))
      (node (ref "U2") (pin "3") (pinfunction "+IN_3") (pintype "input"))
    )
    (net (code "49") (name "Net-(U2A-OUT)") (class "Default")
      (node (ref "LED1") (pin "A") (pinfunction "A_A") (pintype "passive"))
      (node (ref "U2") (pin "1") (pinfunction "OUT_1") (pintype "output"))
    )
    (net (code "50") (name "Net-(U2B--IN)") (class "Default")
      (node (ref "R16") (pin "2") (pinfunction "2_2") (pintype "passive"))
      (node (ref "R20") (pin "1") (pinfunction "1_1") (pintype "passive"))
      (node (ref "U2") (pin "6") (pinfunction "-IN_6") (pintype "input"))
    )
    (net (code "51") (name "Net-(U2B-OUT)") (class "Default")
      (node (ref "R20") (pin "2") (pinfunction "2_2") (pintype "passive"))
      (node (ref "R22") (pin "2") (pinfunction "2_2") (pintype "passive"))
      (node (ref "U2") (pin "7") (pinfunction "OUT_7") (pintype "output"))
    )
    (net (code "52") (name "Net-(U7B--IN)") (class "Default")
      (node (ref "R3") (pin "2") (pinfunction "2_2") (pintype "passive"))
      (node (ref "R6") (pin "2") (pinfunction "2_2") (pintype "passive"))
      (node (ref "U7") (pin "6") (pinfunction "-IN_6") (pintype "input"))
    )
    (net (code "53") (name "Net-(U7B-OUT)") (class "Default")
      (node (ref "R10") (pin "2") (pinfunction "2_2") (pintype "passive"))
      (node (ref "R11") (pin "2") (pinfunction "2_2") (pintype "passive"))
      (node (ref "R6") (pin "1") (pinfunction "1_1") (pintype "passive"))
      (node (ref "U7") (pin "7") (pinfunction "OUT_7") (pintype "output"))
    )
    (net (code "54") (name "Net-(Z$102-+5VDC)") (class "Default")
      (node (ref "78L05") (pin "OUT") (pinfunction "OUT_OUT") (pintype "passive"))
      (node (ref "Z$102") (pin "1") (pinfunction "+5VDC_1") (pintype "bidirectional"))
    )
    (net (code "55") (name "Net-(Z$102-INPUT)") (class "Default")
      (node (ref "R101") (pin "2") (pinfunction "2_2") (pintype "passive"))
      (node (ref "R102") (pin "2") (pinfunction "2_2") (pintype "passive"))
      (node (ref "Z$102") (pin "3") (pinfunction "INPUT_3") (pintype "bidirectional"))
    )
    (net (code "56") (name "Net-(Z$102-OUT1)") (class "Default")
      (node (ref "R104") (pin "1") (pinfunction "1_1") (pintype "passive"))
      (node (ref "Z$102") (pin "6") (pinfunction "OUT1_6") (pintype "bidirectional"))
    )
    (net (code "57") (name "Net-(Z$102-OUT2)") (class "Default")
      (node (ref "R105") (pin "1") (pinfunction "1_1") (pintype "passive"))
      (node (ref "Z$102") (pin "5") (pinfunction "OUT2_5") (pintype "bidirectional"))
    )
    (net (code "58") (name "Net-(Z$102-PWR-GND)") (class "Default")
      (node (ref "78L05") (pin "GND") (pinfunction "GND_GND") (pintype "input"))
      (node (ref "Z$102") (pin "2") (pinfunction "PWR-GND_2") (pintype "bidirectional"))
    )
    (net (code "59") (name "REVERB_RETURN_B") (class "Default")
      (node (ref "IC102") (pin "3") (pinfunction "+IN_3") (pintype "input"))
      (node (ref "J2") (pin "4") (pinfunction "4_4") (pintype "passive"))
      (node (ref "JP102") (pin "2") (pinfunction "2_2") (pintype "passive"))
    )
    (net (code "60") (name "REVERB_RETURN_F") (class "Default")
      (node (ref "J1") (pin "4") (pinfunction "4_4") (pintype "passive"))
      (node (ref "X-FADE") (pin "P$2_SWITCH") (pinfunction "SWITCH_P$2_SWITCH") (pintype "passive"))
    )
    (net (code "61") (name "REVERB_SEND_B") (class "Default")
      (node (ref "C5") (pin "2") (pinfunction "2_2") (pintype "passive"))
      (node (ref "IC102") (pin "10") (pinfunction "+IN_10") (pintype "input"))
      (node (ref "R101") (pin "1") (pinfunction "1_1") (pintype "passive"))
      (node (ref "R18") (pin "2") (pinfunction "2_2") (pintype "passive"))
      (node (ref "R19") (pin "2") (pinfunction "2_2") (pintype "passive"))
      (node (ref "U7") (pin "1") (pinfunction "OUT_1") (pintype "output"))
    )
    (net (code "62") (name "TRIM_B") (class "Default")
      (node (ref "C101") (pin "2") (pinfunction "-_2") (pintype "passive"))
      (node (ref "JP104") (pin "3") (pinfunction "3_3") (pintype "passive"))
    )
    (net (code "63") (name "TRIM_F") (class "Default")
      (node (ref "JP2") (pin "3") (pinfunction "3_3") (pintype "passive"))
      (node (ref "VR1") (pin "1") (pinfunction "1_1") (pintype "passive"))
    )
    (net (code "64") (name "VAC_AN_B") (class "Default")
      (node (ref "JP104") (pin "1") (pinfunction "1_1") (pintype "passive"))
      (node (ref "V$101") (pin "LED+") (pinfunction "LED+_LED+") (pintype "passive"))
    )
    (net (code "65") (name "VAC_AN_F") (class "Default")
      (node (ref "JP2") (pin "1") (pinfunction "1_1") (pintype "passive"))
      (node (ref "LED1") (pin "K") (pinfunction "C_K") (pintype "passive"))
    )
    (net (code "66") (name "VAC_CA_B") (class "Default")
      (node (ref "JP104") (pin "2") (pinfunction "2_2") (pintype "passive"))
      (node (ref "V$101") (pin "LED-") (pinfunction "LED-_LED-") (pintype "passive"))
    )
    (net (code "67") (name "VAC_CA_F") (class "Default")
      (node (ref "JP2") (pin "2") (pinfunction "2_2") (pintype "passive"))
      (node (ref "R24") (pin "1") (pinfunction "1_1") (pintype "passive"))
      (node (ref "U2") (pin "2") (pinfunction "-IN_2") (pintype "input"))
    )
    (net (code "68") (name "WET_B") (class "Default")
      (node (ref "IC102") (pin "1") (pinfunction "OUT_1") (pintype "output"))
      (node (ref "IC102") (pin "2") (pinfunction "-IN_2") (pintype "input"))
      (node (ref "J2") (pin "2") (pinfunction "2_2") (pintype "passive"))
    )
    (net (code "69") (name "WET_F") (class "Default")
      (node (ref "IN_2") (pin "P$2_SWITCH") (pinfunction "SWITCH_P$2_SWITCH") (pintype "passive"))
      (node (ref "J1") (pin "2") (pinfunction "2_2") (pintype "passive"))
      (node (ref "WET_OUT") (pin "P$1_TIP") (pinfunction "TIP_P$1_TIP") (pintype "passive"))
    )
    (net (code "70") (name "XFADE_B") (class "Default")
      (node (ref "IC103") (pin "3") (pinfunction "+IN_3") (pintype "input"))
      (node (ref "J2") (pin "3") (pinfunction "3_3") (pintype "passive"))
    )
    (net (code "71") (name "XFADE_F") (class "Default")
      (node (ref "J1") (pin "3") (pinfunction "3_3") (pintype "passive"))
      (node (ref "X-FADE") (pin "P$1_TIP") (pinfunction "TIP_P$1_TIP") (pintype "passive"))
    )
    (net (code "72") (name "unconnected-(CV-SWITCH-PadP$2_SWITCH)") (class "Default")
      (node (ref "CV") (pin "P$2_SWITCH") (pinfunction "SWITCH_P$2_SWITCH") (pintype "passive"))
    )
    (net (code "73") (name "unconnected-(IN_1-SWITCH-PadP$2_SWITCH)") (class "Default")
      (node (ref "IN_1") (pin "P$2_SWITCH") (pinfunction "SWITCH_P$2_SWITCH") (pintype "passive"))
    )
    (net (code "74") (name "unconnected-(MIX_OUT-SWITCH-PadP$2_SWITCH)") (class "Default")
      (node (ref "MIX_OUT") (pin "P$2_SWITCH") (pinfunction "SWITCH_P$2_SWITCH") (pintype "passive"))
    )
    (net (code "75") (name "unconnected-(WET_OUT-SWITCH-PadP$2_SWITCH)") (class "Default")
      (node (ref "WET_OUT") (pin "P$2_SWITCH") (pinfunction "SWITCH_P$2_SWITCH") (pintype "passive"))
    )
  )
)
